# Sheet1.net
KiCad netlist of a schematic drawn in Altium Designer
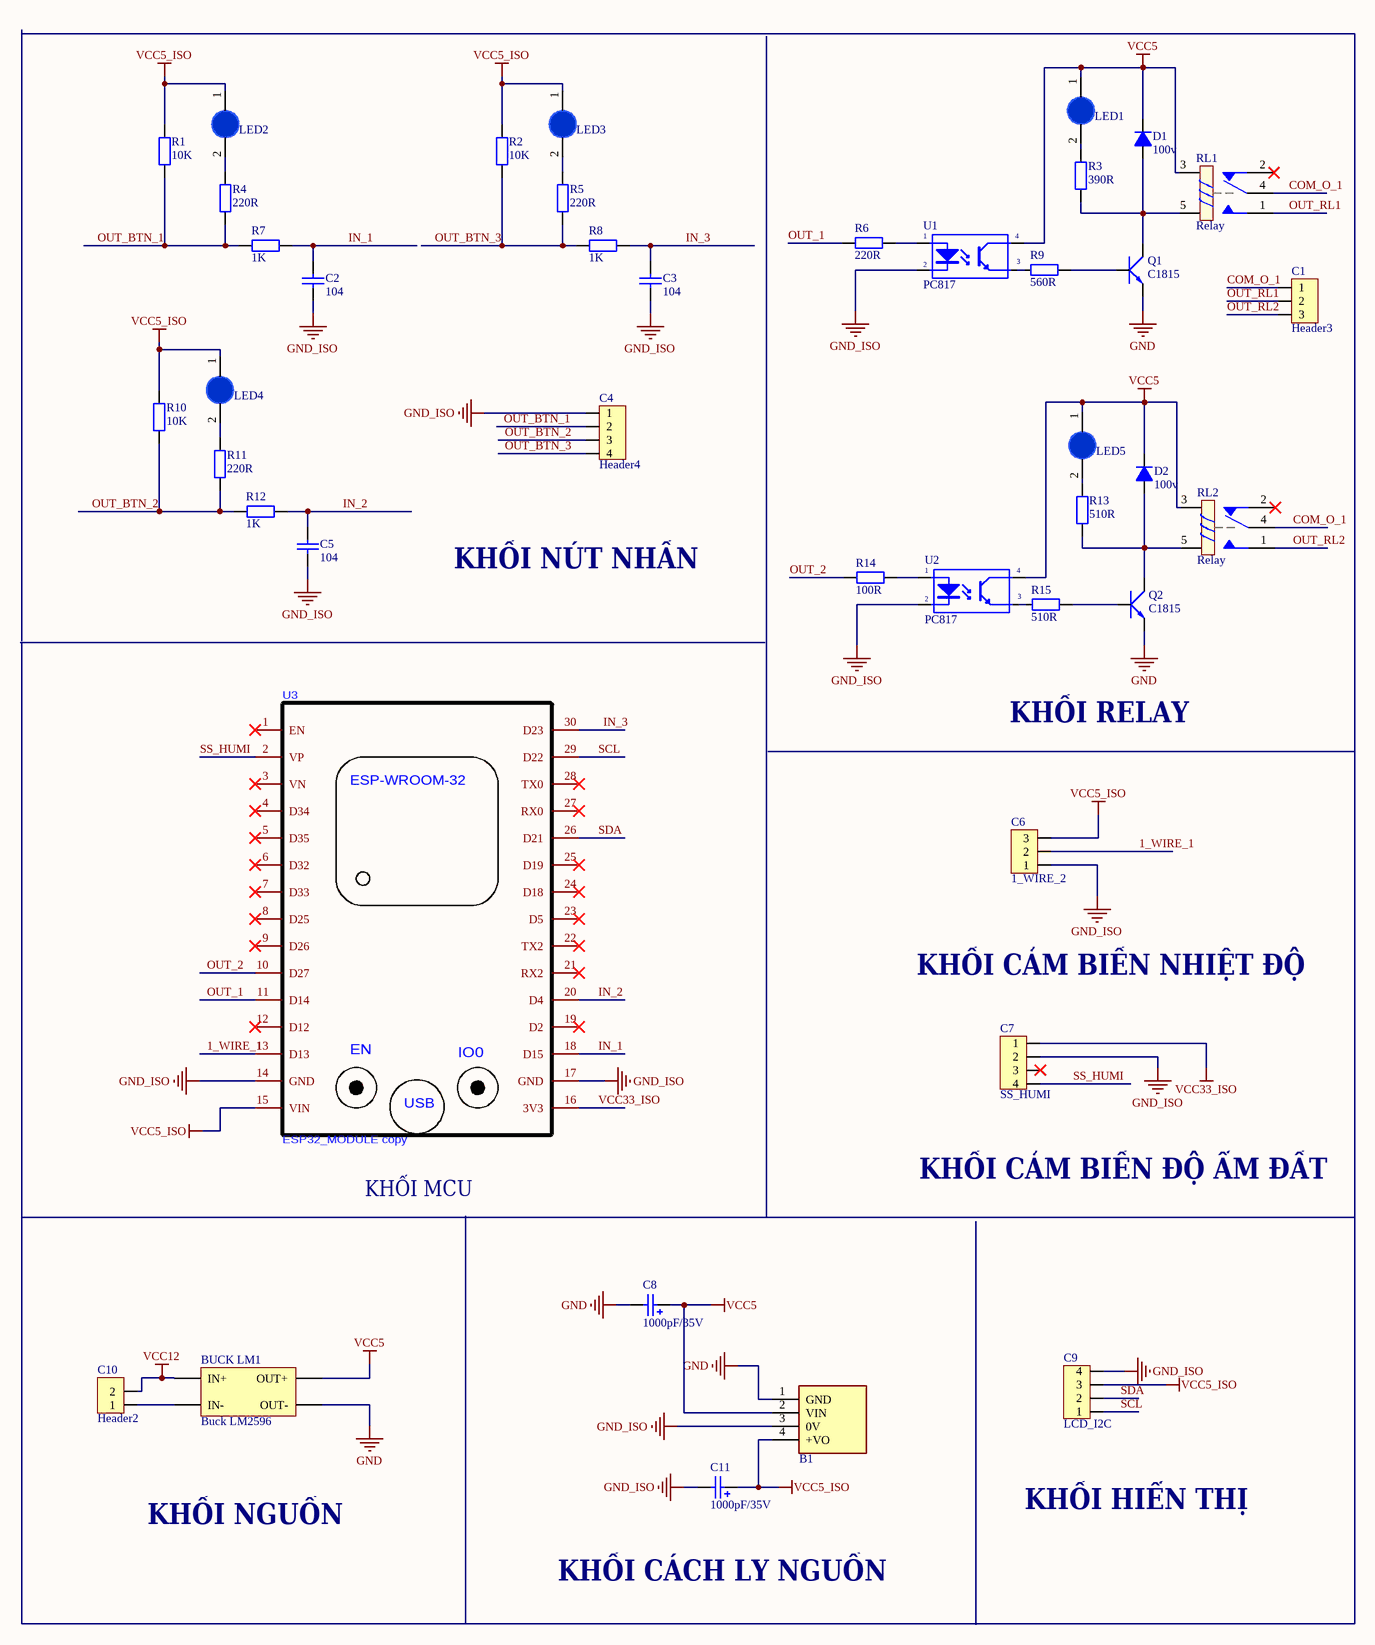
[diagram p0: Sheet1.SchDoc]

(export (version "E")
  (design (tool "Eeschema 10.0.6"))
  (components
    (comp (ref "B1")
      (value "B0505S1W")
      (footprint "B0505S1W")
      (description "Power Supply")
      (fields (field (name "MANUFACTURER_PART_NUMBER") "B0505S-1W"))
      (libsource (lib "myLib_v1") (part "B0505S1W"))
    )
    (comp (ref "BUCK LM1")
      (value "Buck LM2596")
      (footprint "BUCK LM2596")
      (libsource (lib "myLib_v1") (part "Buck LM2596"))
    )
    (comp (ref "C1")
      (value "Header3")
      (footprint "Header3")
      (description "Header IDC, 3 x 1 Pin Vertical 2.54mm Pitch (Non-Boxed, Male)")
      (fields
        (field (name "MANUFACTURER") "Würth Elektronik eiSos GmbH")
        (field (name "PARTNO") "613002143121")
        (field (name "CREATED BY") "Karrer Zheng")
      )
      (libsource (lib "") (part "Header3_1"))
    )
    (comp (ref "C2")
      (value "104")
      (footprint "tu gom")
      (description "Cắm")
      (libsource (lib "Altium_Lib_by_KhueNguyenCreator") (part "Tu gom 104 50V"))
    )
    (comp (ref "C3")
      (value "104")
      (footprint "tu gom")
      (description "Cắm")
      (libsource (lib "Altium_Lib_by_KhueNguyenCreator") (part "Tu gom 104 50V"))
    )
    (comp (ref "C4")
      (value "Header4")
      (footprint "Header4")
      (description "Header IDC, 4 x 1 Pin Vertical 2.54mm Pitch (Non-Boxed, Male)")
      (fields
        (field (name "MANUFACTURER") "Würth Elektronik eiSos GmbH")
        (field (name "PARTNO") "613002143121")
        (field (name "CREATED BY") "Karrer Zheng")
      )
      (libsource (lib "") (part "Header4_1"))
    )
    (comp (ref "C5")
      (value "104")
      (footprint "tu gom")
      (description "Cắm")
      (libsource (lib "Altium_Lib_by_KhueNguyenCreator") (part "Tu gom 104 50V"))
    )
    (comp (ref "C6")
      (value "1_WIRE_2")
      (footprint "Header3")
      (description "Header IDC, 3 x 1 Pin Vertical 2.54mm Pitch (Non-Boxed, Male)")
      (fields
        (field (name "MANUFACTURER") "Würth Elektronik eiSos GmbH")
        (field (name "PARTNO") "613002143121")
        (field (name "CREATED BY") "Karrer Zheng")
      )
      (libsource (lib "myLib_v1") (part "Header3"))
    )
    (comp (ref "C7")
      (value "SS_HUMI")
      (footprint "Header4")
      (description "Header IDC, 4 x 1 Pin Vertical 2.54mm Pitch (Non-Boxed, Male)")
      (fields
        (field (name "MANUFACTURER") "Würth Elektronik eiSos GmbH")
        (field (name "PARTNO") "613002143121")
        (field (name "CREATED BY") "Karrer Zheng")
      )
      (libsource (lib "") (part "Header4_2"))
    )
    (comp (ref "C8")
      (value "1000pF/35V")
      (footprint "CP2/5")
      (description "Polarized Capacitor (Surface Mount)")
      (fields (field (name "Comment") "Cap Pol3") (field (name "PUBLISHER") "Altium Limited"))
      (libsource (lib "myLib_v1") (part "Cap Pol3"))
    )
    (comp (ref "C9")
      (value "LCD_I2C")
      (footprint "Header4")
      (description "Header IDC, 4 x 1 Pin Vertical 2.54mm Pitch (Non-Boxed, Male)")
      (fields
        (field (name "MANUFACTURER") "Würth Elektronik eiSos GmbH")
        (field (name "PARTNO") "613002143121")
        (field (name "CREATED BY") "Karrer Zheng")
      )
      (libsource (lib "myLib_v1") (part "Header4"))
    )
    (comp (ref "C10")
      (value "Header2")
      (footprint "Header2")
      (description "Header IDC, 2 x 1 Pin Vertical 2.54mm Pitch (Non-Boxed, Male)")
      (fields
        (field (name "MANUFACTURER") "Würth Elektronik eiSos GmbH")
        (field (name "PARTNO") "613002143121")
        (field (name "CREATED BY") "Karrer Zheng")
      )
      (libsource (lib "myLib_v1") (part "Header2"))
    )
    (comp (ref "C11")
      (value "1000pF/35V")
      (footprint "CP2/5")
      (description "Polarized Capacitor (Surface Mount)")
      (fields (field (name "Comment") "Cap Pol3") (field (name "PUBLISHER") "Altium Limited"))
      (libsource (lib "myLib_v1") (part "Cap Pol3"))
    )
    (comp (ref "D1")
      (value "100v")
      (footprint "DIODE 0.5A")
      (description "Cắm")
      (libsource (lib "Altium_Lib_by_KhueNguyenCreator") (part "Diode 1N4148"))
    )
    (comp (ref "D2")
      (value "100v")
      (footprint "DIODE 0.5A")
      (description "Cắm")
      (libsource (lib "Altium_Lib_by_KhueNguyenCreator") (part "Diode 1N4148"))
    )
    (comp (ref "LED1")
      (value "LED 3mm")
      (footprint "LED-3MM-BLUE")
      (description "Cắm")
      (libsource (lib "myLib_v1") (part "LED 3mm Xanh Duong"))
    )
    (comp (ref "LED2")
      (value "LED 3mm")
      (footprint "LED-3MM-BLUE")
      (description "Cắm")
      (libsource (lib "myLib_v1") (part "LED 3mm Xanh Duong"))
    )
    (comp (ref "LED3")
      (value "LED 3mm")
      (footprint "LED-3MM-BLUE")
      (description "Cắm")
      (libsource (lib "myLib_v1") (part "LED 3mm Xanh Duong"))
    )
    (comp (ref "LED4")
      (value "LED 3mm")
      (footprint "LED-3MM-BLUE")
      (description "Cắm")
      (libsource (lib "myLib_v1") (part "LED 3mm Xanh Duong"))
    )
    (comp (ref "LED5")
      (value "LED 3mm")
      (footprint "LED-3MM-BLUE")
      (description "Cắm")
      (libsource (lib "myLib_v1") (part "LED 3mm Xanh Duong"))
    )
    (comp (ref "Q1")
      (value "C1815")
      (footprint "C1815_cam")
      (description "NPN 600mW, ECB")
      (libsource (lib "myLib_v1") (part "C1815"))
    )
    (comp (ref "Q2")
      (value "C1815")
      (footprint "C1815_cam")
      (description "NPN 600mW, ECB")
      (libsource (lib "myLib_v1") (part "C1815"))
    )
    (comp (ref "R1")
      (value "10K")
      (footprint "R1/4W")
      (description "Resistor 1/4W")
      (libsource (lib "myLib_v1") (part "R1/4W"))
    )
    (comp (ref "R2")
      (value "10K")
      (footprint "R1/4W")
      (description "Resistor 1/4W")
      (libsource (lib "myLib_v1") (part "R1/4W"))
    )
    (comp (ref "R3")
      (value "390R")
      (footprint "R1/4W")
      (description "Resistor 1/4W")
      (libsource (lib "myLib_v1") (part "R1/4W"))
    )
    (comp (ref "R4")
      (value "220R")
      (footprint "R1/4W")
      (description "Resistor 1/4W")
      (libsource (lib "myLib_v1") (part "R1/4W"))
    )
    (comp (ref "R5")
      (value "220R")
      (footprint "R1/4W")
      (description "Resistor 1/4W")
      (libsource (lib "myLib_v1") (part "R1/4W"))
    )
    (comp (ref "R6")
      (value "220R")
      (footprint "R1/4W")
      (description "Resistor 1/4W")
      (libsource (lib "myLib_v1") (part "R1/4W"))
    )
    (comp (ref "R7")
      (value "1K")
      (footprint "R1/4W")
      (description "Resistor 1/4W")
      (libsource (lib "myLib_v1") (part "R1/4W"))
    )
    (comp (ref "R8")
      (value "1K")
      (footprint "R1/4W")
      (description "Resistor 1/4W")
      (libsource (lib "myLib_v1") (part "R1/4W"))
    )
    (comp (ref "R9")
      (value "560R")
      (footprint "R1/4W")
      (description "Resistor 1/4W")
      (libsource (lib "myLib_v1") (part "R1/4W"))
    )
    (comp (ref "R10")
      (value "10K")
      (footprint "R1/4W")
      (description "Resistor 1/4W")
      (libsource (lib "myLib_v1") (part "R1/4W"))
    )
    (comp (ref "R11")
      (value "220R")
      (footprint "R1/4W")
      (description "Resistor 1/4W")
      (libsource (lib "myLib_v1") (part "R1/4W"))
    )
    (comp (ref "R12")
      (value "1K")
      (footprint "R1/4W")
      (description "Resistor 1/4W")
      (libsource (lib "myLib_v1") (part "R1/4W"))
    )
    (comp (ref "R13")
      (value "510R")
      (footprint "R1/4W")
      (description "Resistor 1/4W")
      (libsource (lib "myLib_v1") (part "R1/4W"))
    )
    (comp (ref "R14")
      (value "100R")
      (footprint "R1/4W")
      (description "Resistor 1/4W")
      (libsource (lib "myLib_v1") (part "R1/4W"))
    )
    (comp (ref "R15")
      (value "510R")
      (footprint "R1/4W")
      (description "Resistor 1/4W")
      (libsource (lib "myLib_v1") (part "R1/4W"))
    )
    (comp (ref "RL1")
      (value "Relay")
      (footprint "RELAY_SRA_05VDC_SL_C")
      (description "Relay 5 Chan")
      (libsource (lib "myLib_v1") (part "RL_SRA-05VDC-SL-C"))
    )
    (comp (ref "RL2")
      (value "Relay")
      (footprint "RELAY_SRA_05VDC_SL_C")
      (description "Relay 5 Chan")
      (libsource (lib "myLib_v1") (part "RL_SRA-05VDC-SL-C"))
    )
    (comp (ref "U1")
      (value "PC817")
      (footprint "DIP4/W0.3")
      (description "Single Opto")
      (libsource (lib "myLib_v1") (part "PC817"))
    )
    (comp (ref "U2")
      (value "PC817")
      (footprint "DIP4/W0.3")
      (description "Single Opto")
      (libsource (lib "myLib_v1") (part "PC817"))
    )
    (comp (ref "U3")
      (value "ESP32_MODULE copy")
      (footprint "ESP32-WIFIMODULE-FOOTPRINT")
      (libsource (lib "myLib_v1") (part "ESP32_MODULE copy"))
    )
  )
  (nets
    (net (code "1") (name "/1_WIRE_1") (class "Default")
      (node (ref "C6") (pin "2") (pinfunction "2_2") (pintype "passive"))
      (node (ref "U3") (pin "13") (pinfunction "D13_13") (pintype "passive"))
    )
    (net (code "2") (name "/COM_O_1") (class "Default")
      (node (ref "C1") (pin "1") (pinfunction "1_1") (pintype "passive"))
      (node (ref "RL1") (pin "4") (pinfunction "4_4") (pintype "passive"))
      (node (ref "RL2") (pin "4") (pinfunction "4_4") (pintype "passive"))
    )
    (net (code "3") (name "/IN_1") (class "Default")
      (node (ref "C2") (pin "1") (pinfunction "1_1") (pintype "passive"))
      (node (ref "R7") (pin "1") (pinfunction "1_1") (pintype "passive"))
      (node (ref "U3") (pin "18") (pinfunction "D15_18") (pintype "passive"))
    )
    (net (code "4") (name "/IN_2") (class "Default")
      (node (ref "C5") (pin "1") (pinfunction "1_1") (pintype "passive"))
      (node (ref "R12") (pin "1") (pinfunction "1_1") (pintype "passive"))
      (node (ref "U3") (pin "20") (pinfunction "D4_20") (pintype "passive"))
    )
    (net (code "5") (name "/IN_3") (class "Default")
      (node (ref "C3") (pin "1") (pinfunction "1_1") (pintype "passive"))
      (node (ref "R8") (pin "1") (pinfunction "1_1") (pintype "passive"))
      (node (ref "U3") (pin "30") (pinfunction "D23_30") (pintype "passive"))
    )
    (net (code "6") (name "/OUT_1") (class "Default")
      (node (ref "R6") (pin "1") (pinfunction "1_1") (pintype "passive"))
      (node (ref "U3") (pin "11") (pinfunction "D14_11") (pintype "passive"))
    )
    (net (code "7") (name "/OUT_2") (class "Default")
      (node (ref "R14") (pin "1") (pinfunction "1_1") (pintype "passive"))
      (node (ref "U3") (pin "10") (pinfunction "D27_10") (pintype "passive"))
    )
    (net (code "8") (name "/OUT_BTN_1") (class "Default")
      (node (ref "C4") (pin "2") (pinfunction "2_2") (pintype "passive"))
      (node (ref "R1") (pin "1") (pinfunction "1_1") (pintype "passive"))
      (node (ref "R4") (pin "1") (pinfunction "1_1") (pintype "passive"))
      (node (ref "R7") (pin "2") (pinfunction "2_2") (pintype "passive"))
    )
    (net (code "9") (name "/OUT_BTN_2") (class "Default")
      (node (ref "C4") (pin "3") (pinfunction "3_3") (pintype "passive"))
      (node (ref "R10") (pin "1") (pinfunction "1_1") (pintype "passive"))
      (node (ref "R11") (pin "1") (pinfunction "1_1") (pintype "passive"))
      (node (ref "R12") (pin "2") (pinfunction "2_2") (pintype "passive"))
    )
    (net (code "10") (name "/OUT_BTN_3") (class "Default")
      (node (ref "C4") (pin "4") (pinfunction "4_4") (pintype "passive"))
      (node (ref "R2") (pin "1") (pinfunction "1_1") (pintype "passive"))
      (node (ref "R5") (pin "1") (pinfunction "1_1") (pintype "passive"))
      (node (ref "R8") (pin "2") (pinfunction "2_2") (pintype "passive"))
    )
    (net (code "11") (name "/OUT_RL1") (class "Default")
      (node (ref "C1") (pin "2") (pinfunction "2_2") (pintype "passive"))
      (node (ref "RL1") (pin "1") (pinfunction "1_1") (pintype "passive"))
    )
    (net (code "12") (name "/OUT_RL2") (class "Default")
      (node (ref "C1") (pin "3") (pinfunction "3_3") (pintype "passive"))
      (node (ref "RL2") (pin "1") (pinfunction "1_1") (pintype "passive"))
    )
    (net (code "13") (name "/SCL") (class "Default")
      (node (ref "C9") (pin "1") (pinfunction "1_1") (pintype "passive"))
      (node (ref "U3") (pin "29") (pinfunction "D22_29") (pintype "passive"))
    )
    (net (code "14") (name "/SDA") (class "Default")
      (node (ref "C9") (pin "2") (pinfunction "2_2") (pintype "passive"))
      (node (ref "U3") (pin "26") (pinfunction "D21_26") (pintype "passive"))
    )
    (net (code "15") (name "/SS_HUMI") (class "Default")
      (node (ref "C7") (pin "4") (pinfunction "4_4") (pintype "passive"))
      (node (ref "U3") (pin "2") (pinfunction "VP_2") (pintype "passive"))
    )
    (net (code "16") (name "GND") (class "Default")
      (node (ref "B1") (pin "1") (pinfunction "GND_1") (pintype "passive"))
      (node (ref "BUCK LM1") (pin "3") (pinfunction "OUT-_3") (pintype "passive"))
      (node (ref "C8") (pin "2") (pinfunction "2_2") (pintype "passive"))
      (node (ref "Q1") (pin "1") (pinfunction "E_1") (pintype "passive"))
      (node (ref "Q2") (pin "1") (pinfunction "E_1") (pintype "passive"))
    )
    (net (code "17") (name "GND_ISO") (class "Default")
      (node (ref "B1") (pin "3") (pinfunction "0V_3") (pintype "passive"))
      (node (ref "C11") (pin "2") (pinfunction "2_2") (pintype "passive"))
      (node (ref "C2") (pin "2") (pinfunction "2_2") (pintype "passive"))
      (node (ref "C3") (pin "2") (pinfunction "2_2") (pintype "passive"))
      (node (ref "C4") (pin "1") (pinfunction "1_1") (pintype "passive"))
      (node (ref "C5") (pin "2") (pinfunction "2_2") (pintype "passive"))
      (node (ref "C6") (pin "1") (pinfunction "1_1") (pintype "passive"))
      (node (ref "C7") (pin "2") (pinfunction "2_2") (pintype "passive"))
      (node (ref "C9") (pin "4") (pinfunction "4_4") (pintype "passive"))
      (node (ref "U1") (pin "2") (pinfunction "K_2") (pintype "passive"))
      (node (ref "U2") (pin "2") (pinfunction "K_2") (pintype "passive"))
      (node (ref "U3") (pin "14") (pinfunction "GND_14") (pintype "passive"))
      (node (ref "U3") (pin "17") (pinfunction "GND_17") (pintype "passive"))
    )
    (net (code "18") (name "Net-(BUCK LM1-IN-)") (class "Default")
      (node (ref "BUCK LM1") (pin "2") (pinfunction "IN-_2") (pintype "passive"))
      (node (ref "C10") (pin "1") (pinfunction "1_1") (pintype "passive"))
    )
    (net (code "19") (name "Net-(D1-A)") (class "Default")
      (node (ref "D1") (pin "1") (pinfunction "A_1") (pintype "passive"))
      (node (ref "Q1") (pin "2") (pinfunction "C_2") (pintype "passive"))
      (node (ref "R3") (pin "2") (pinfunction "2_2") (pintype "passive"))
      (node (ref "RL1") (pin "5") (pinfunction "5_5") (pintype "passive"))
    )
    (net (code "20") (name "Net-(D2-A)") (class "Default")
      (node (ref "D2") (pin "1") (pinfunction "A_1") (pintype "passive"))
      (node (ref "Q2") (pin "2") (pinfunction "C_2") (pintype "passive"))
      (node (ref "R13") (pin "2") (pinfunction "2_2") (pintype "passive"))
      (node (ref "RL2") (pin "5") (pinfunction "5_5") (pintype "passive"))
    )
    (net (code "21") (name "Net-(LED1-K)") (class "Default")
      (node (ref "LED1") (pin "2") (pinfunction "K_2") (pintype "passive"))
      (node (ref "R3") (pin "1") (pinfunction "1_1") (pintype "passive"))
    )
    (net (code "22") (name "Net-(LED2-K)") (class "Default")
      (node (ref "LED2") (pin "2") (pinfunction "K_2") (pintype "passive"))
      (node (ref "R4") (pin "2") (pinfunction "2_2") (pintype "passive"))
    )
    (net (code "23") (name "Net-(LED3-K)") (class "Default")
      (node (ref "LED3") (pin "2") (pinfunction "K_2") (pintype "passive"))
      (node (ref "R5") (pin "2") (pinfunction "2_2") (pintype "passive"))
    )
    (net (code "24") (name "Net-(LED4-K)") (class "Default")
      (node (ref "LED4") (pin "2") (pinfunction "K_2") (pintype "passive"))
      (node (ref "R11") (pin "2") (pinfunction "2_2") (pintype "passive"))
    )
    (net (code "25") (name "Net-(LED5-K)") (class "Default")
      (node (ref "LED5") (pin "2") (pinfunction "K_2") (pintype "passive"))
      (node (ref "R13") (pin "1") (pinfunction "1_1") (pintype "passive"))
    )
    (net (code "26") (name "Net-(Q1-B)") (class "Default")
      (node (ref "Q1") (pin "3") (pinfunction "B_3") (pintype "passive"))
      (node (ref "R9") (pin "2") (pinfunction "2_2") (pintype "passive"))
    )
    (net (code "27") (name "Net-(Q2-B)") (class "Default")
      (node (ref "Q2") (pin "3") (pinfunction "B_3") (pintype "passive"))
      (node (ref "R15") (pin "2") (pinfunction "2_2") (pintype "passive"))
    )
    (net (code "28") (name "Net-(U1-A)") (class "Default")
      (node (ref "R6") (pin "2") (pinfunction "2_2") (pintype "passive"))
      (node (ref "U1") (pin "1") (pinfunction "A_1") (pintype "passive"))
    )
    (net (code "29") (name "Net-(U1-E)") (class "Default")
      (node (ref "R9") (pin "1") (pinfunction "1_1") (pintype "passive"))
      (node (ref "U1") (pin "3") (pinfunction "E_3") (pintype "passive"))
    )
    (net (code "30") (name "Net-(U2-A)") (class "Default")
      (node (ref "R14") (pin "2") (pinfunction "2_2") (pintype "passive"))
      (node (ref "U2") (pin "1") (pinfunction "A_1") (pintype "passive"))
    )
    (net (code "31") (name "Net-(U2-E)") (class "Default")
      (node (ref "R15") (pin "1") (pinfunction "1_1") (pintype "passive"))
      (node (ref "U2") (pin "3") (pinfunction "E_3") (pintype "passive"))
    )
    (net (code "32") (name "VCC5") (class "Default")
      (node (ref "B1") (pin "2") (pinfunction "VIN_2") (pintype "passive"))
      (node (ref "BUCK LM1") (pin "4") (pinfunction "OUT+_4") (pintype "passive"))
      (node (ref "C8") (pin "1") (pinfunction "1_1") (pintype "passive"))
      (node (ref "D1") (pin "2") (pinfunction "K_2") (pintype "passive"))
      (node (ref "D2") (pin "2") (pinfunction "K_2") (pintype "passive"))
      (node (ref "LED1") (pin "1") (pinfunction "A_1") (pintype "passive"))
      (node (ref "LED5") (pin "1") (pinfunction "A_1") (pintype "passive"))
      (node (ref "RL1") (pin "3") (pinfunction "3_3") (pintype "passive"))
      (node (ref "RL2") (pin "3") (pinfunction "3_3") (pintype "passive"))
      (node (ref "U1") (pin "4") (pinfunction "C_4") (pintype "passive"))
      (node (ref "U2") (pin "4") (pinfunction "C_4") (pintype "passive"))
    )
    (net (code "33") (name "VCC5_ISO") (class "Default")
      (node (ref "B1") (pin "4") (pinfunction "+VO_4") (pintype "passive"))
      (node (ref "C11") (pin "1") (pinfunction "1_1") (pintype "passive"))
      (node (ref "C6") (pin "3") (pinfunction "3_3") (pintype "passive"))
      (node (ref "C9") (pin "3") (pinfunction "3_3") (pintype "passive"))
      (node (ref "LED2") (pin "1") (pinfunction "A_1") (pintype "passive"))
      (node (ref "LED3") (pin "1") (pinfunction "A_1") (pintype "passive"))
      (node (ref "LED4") (pin "1") (pinfunction "A_1") (pintype "passive"))
      (node (ref "R1") (pin "2") (pinfunction "2_2") (pintype "passive"))
      (node (ref "R10") (pin "2") (pinfunction "2_2") (pintype "passive"))
      (node (ref "R2") (pin "2") (pinfunction "2_2") (pintype "passive"))
      (node (ref "U3") (pin "15") (pinfunction "VIN_15") (pintype "passive"))
    )
    (net (code "34") (name "VCC12") (class "Default")
      (node (ref "BUCK LM1") (pin "1") (pinfunction "IN+_1") (pintype "passive"))
      (node (ref "C10") (pin "2") (pinfunction "2_2") (pintype "passive"))
    )
    (net (code "35") (name "VCC33_ISO") (class "Default")
      (node (ref "C7") (pin "1") (pinfunction "1_1") (pintype "passive"))
      (node (ref "U3") (pin "16") (pinfunction "3V3_16") (pintype "passive"))
    )
    (net (code "36") (name "unconnected-(C7-Pad3)") (class "Default")
      (node (ref "C7") (pin "3") (pinfunction "3_3") (pintype "passive+no_connect"))
    )
    (net (code "37") (name "unconnected-(RL1-Pad2)") (class "Default")
      (node (ref "RL1") (pin "2") (pinfunction "2_2") (pintype "passive+no_connect"))
    )
    (net (code "38") (name "unconnected-(RL2-Pad2)") (class "Default")
      (node (ref "RL2") (pin "2") (pinfunction "2_2") (pintype "passive+no_connect"))
    )
    (net (code "39") (name "unconnected-(U3-D2-Pad19)") (class "Default")
      (node (ref "U3") (pin "19") (pinfunction "D2_19") (pintype "passive+no_connect"))
    )
    (net (code "40") (name "unconnected-(U3-D5-Pad23)") (class "Default")
      (node (ref "U3") (pin "23") (pinfunction "D5_23") (pintype "passive+no_connect"))
    )
    (net (code "41") (name "unconnected-(U3-D12-Pad12)") (class "Default")
      (node (ref "U3") (pin "12") (pinfunction "D12_12") (pintype "passive+no_connect"))
    )
    (net (code "42") (name "unconnected-(U3-D18-Pad24)") (class "Default")
      (node (ref "U3") (pin "24") (pinfunction "D18_24") (pintype "passive+no_connect"))
    )
    (net (code "43") (name "unconnected-(U3-D19-Pad25)") (class "Default")
      (node (ref "U3") (pin "25") (pinfunction "D19_25") (pintype "passive+no_connect"))
    )
    (net (code "44") (name "unconnected-(U3-D25-Pad8)") (class "Default")
      (node (ref "U3") (pin "8") (pinfunction "D25_8") (pintype "passive+no_connect"))
    )
    (net (code "45") (name "unconnected-(U3-D26-Pad9)") (class "Default")
      (node (ref "U3") (pin "9") (pinfunction "D26_9") (pintype "passive+no_connect"))
    )
    (net (code "46") (name "unconnected-(U3-D32-Pad6)") (class "Default")
      (node (ref "U3") (pin "6") (pinfunction "D32_6") (pintype "passive+no_connect"))
    )
    (net (code "47") (name "unconnected-(U3-D33-Pad7)") (class "Default")
      (node (ref "U3") (pin "7") (pinfunction "D33_7") (pintype "passive+no_connect"))
    )
    (net (code "48") (name "unconnected-(U3-D34-Pad4)") (class "Default")
      (node (ref "U3") (pin "4") (pinfunction "D34_4") (pintype "passive+no_connect"))
    )
    (net (code "49") (name "unconnected-(U3-D35-Pad5)") (class "Default")
      (node (ref "U3") (pin "5") (pinfunction "D35_5") (pintype "passive+no_connect"))
    )
    (net (code "50") (name "unconnected-(U3-EN-Pad1)") (class "Default")
      (node (ref "U3") (pin "1") (pinfunction "EN_1") (pintype "passive+no_connect"))
    )
    (net (code "51") (name "unconnected-(U3-RX0-Pad27)") (class "Default")
      (node (ref "U3") (pin "27") (pinfunction "RX0_27") (pintype "passive+no_connect"))
    )
    (net (code "52") (name "unconnected-(U3-RX2-Pad21)") (class "Default")
      (node (ref "U3") (pin "21") (pinfunction "RX2_21") (pintype "passive+no_connect"))
    )
    (net (code "53") (name "unconnected-(U3-TX0-Pad28)") (class "Default")
      (node (ref "U3") (pin "28") (pinfunction "TX0_28") (pintype "passive+no_connect"))
    )
    (net (code "54") (name "unconnected-(U3-TX2-Pad22)") (class "Default")
      (node (ref "U3") (pin "22") (pinfunction "TX2_22") (pintype "passive+no_connect"))
    )
    (net (code "55") (name "unconnected-(U3-VN-Pad3)") (class "Default")
      (node (ref "U3") (pin "3") (pinfunction "VN_3") (pintype "passive+no_connect"))
    )
  )
)
